# Power_Supply_V3.net
KiCad netlist of a schematic drawn in EAGLE
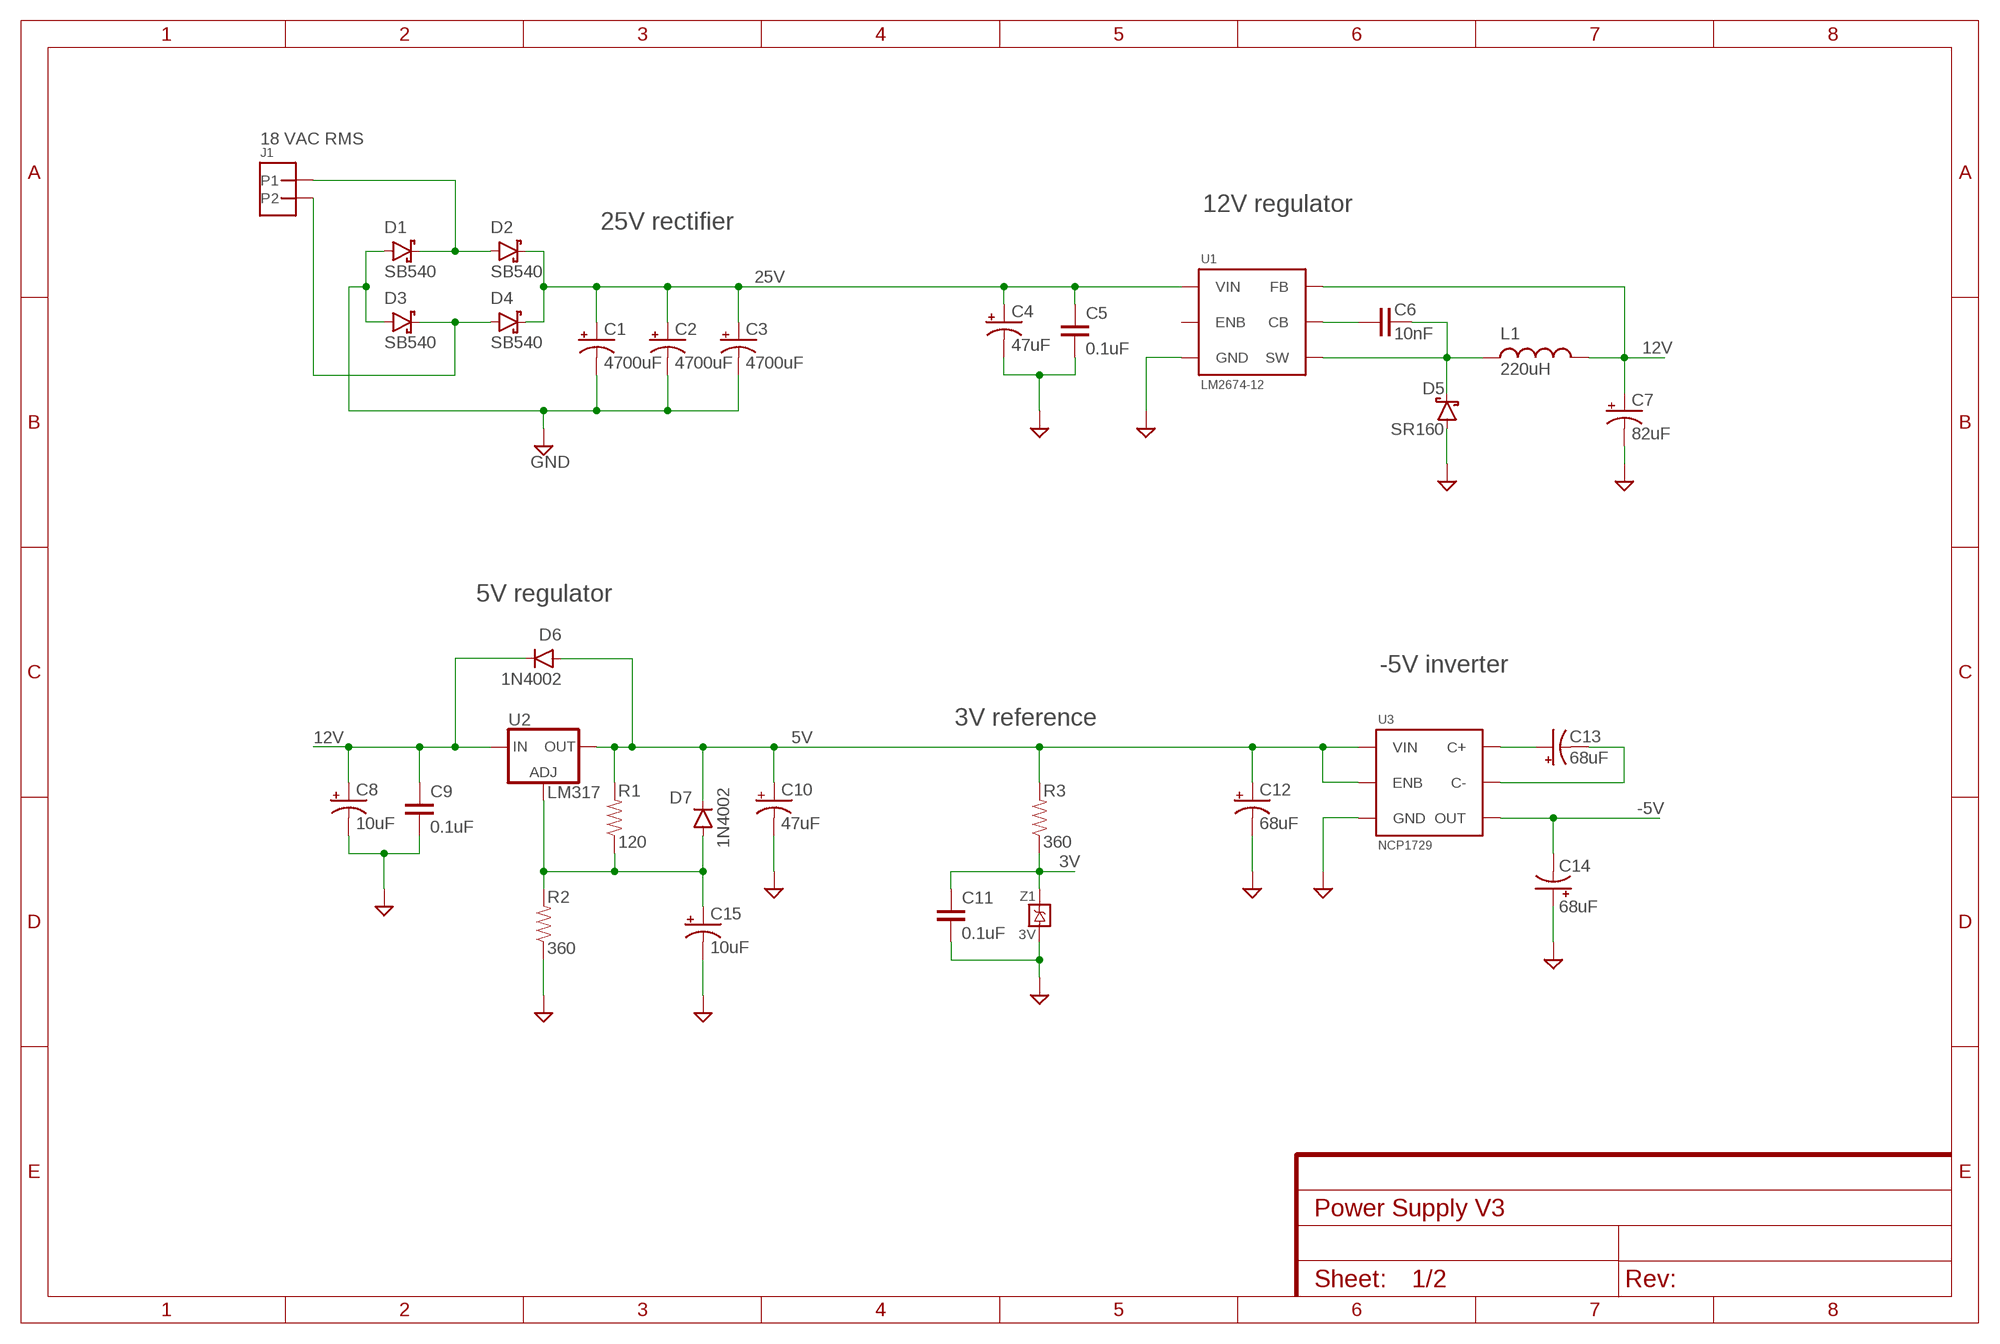
[diagram p0: schematic, sheet 1]
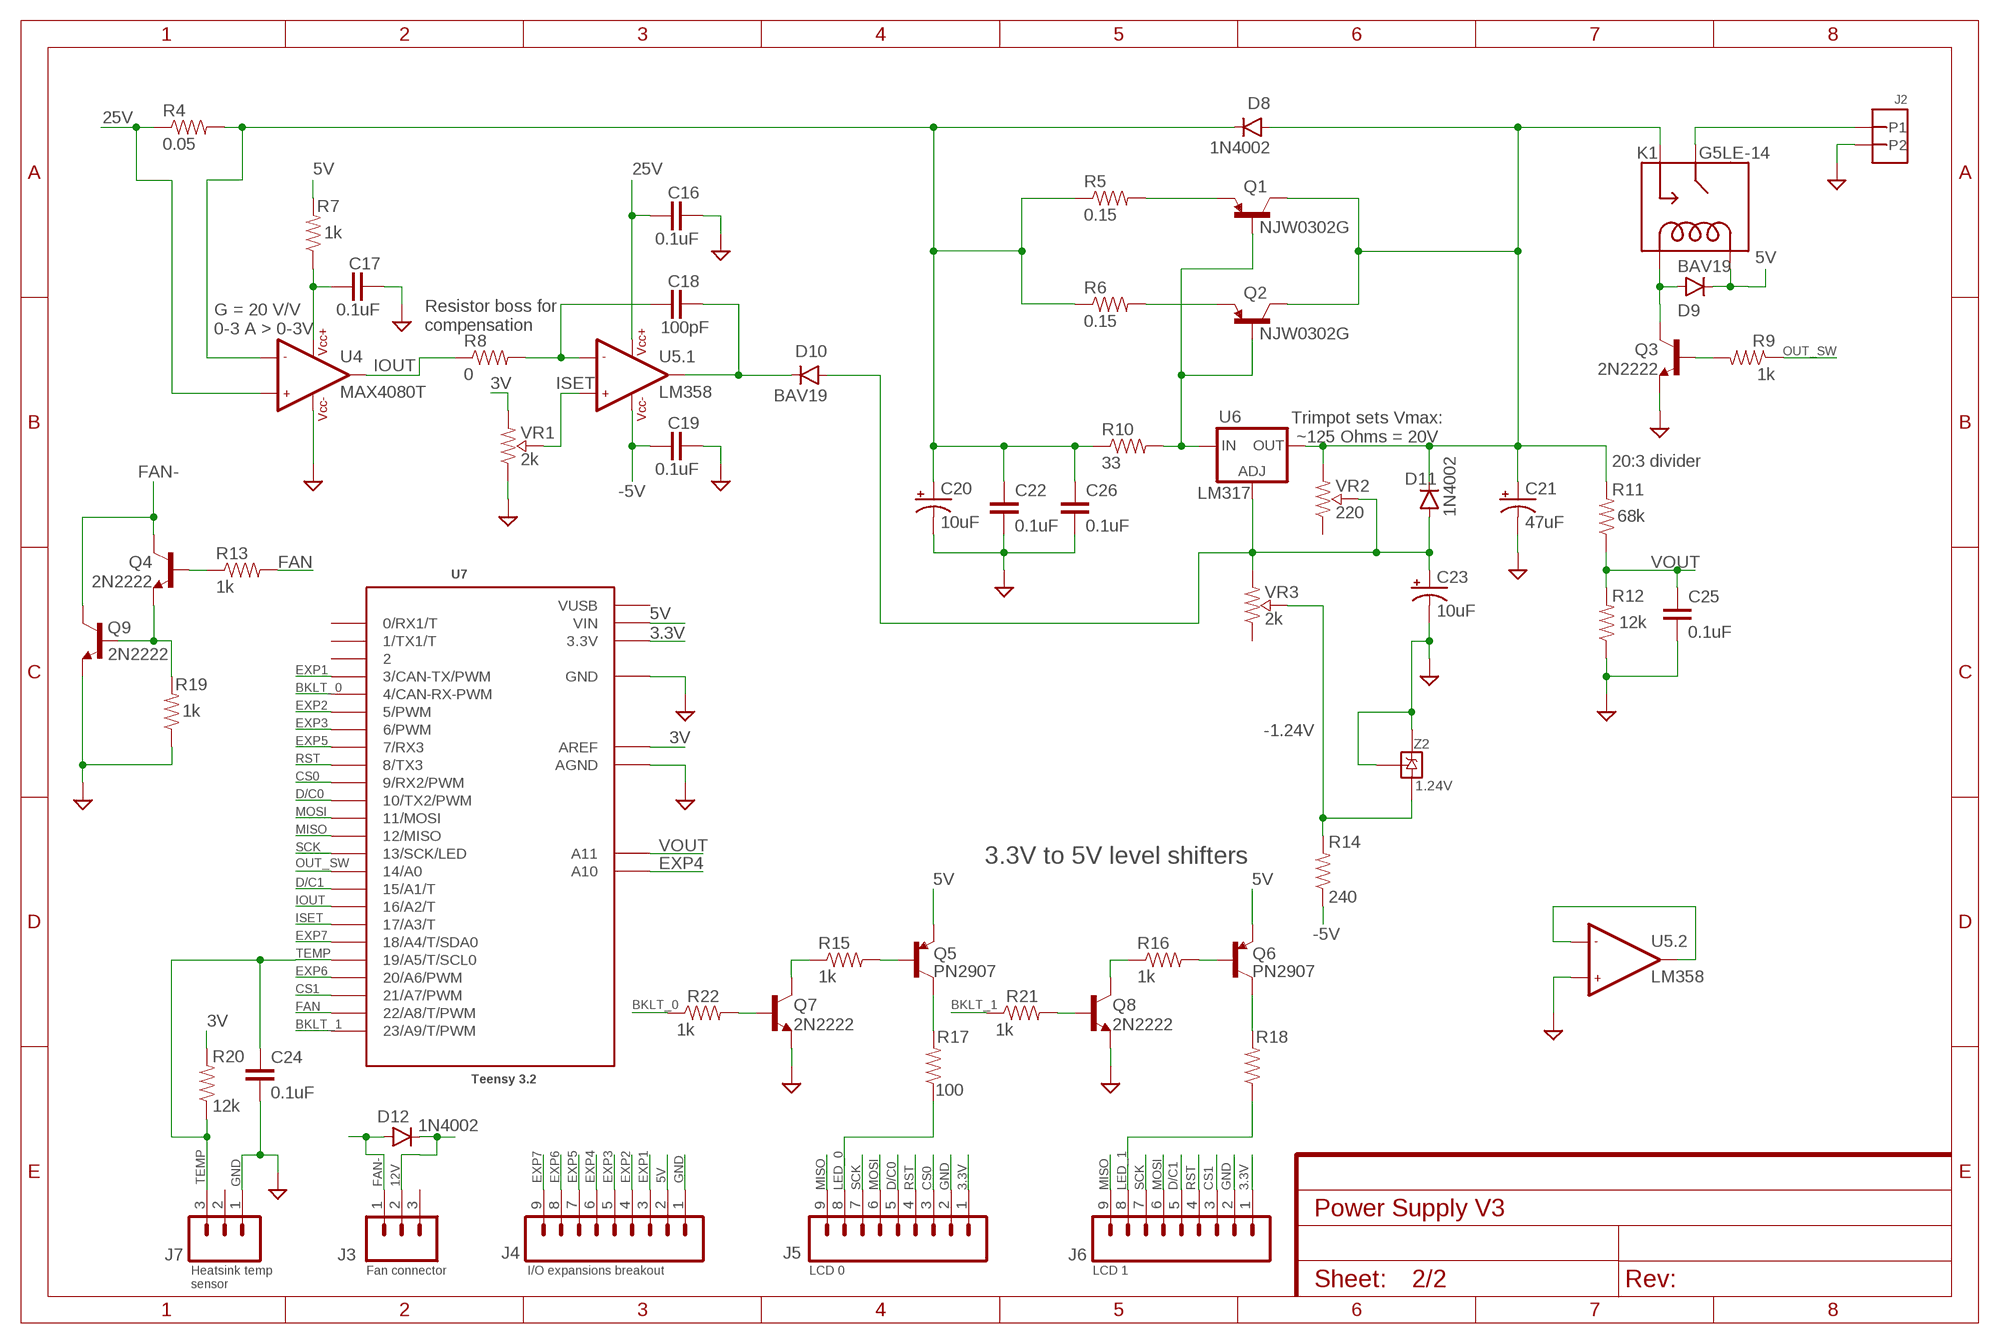
[diagram p1: schematic, sheet 2]

(export (version "E")
  (design (tool "Eeschema 10.0.6"))
  (components
    (comp (ref "C1")
      (value "4700uF")
      (footprint "eagle-import:10MM-LEAD_22MM-DIA")
      (libsource (lib "eagle-import") (part "RADIAL_POL10MM_LEAD-22MM_DIA"))
    )
    (comp (ref "C2")
      (value "4700uF")
      (footprint "eagle-import:10MM-LEAD_22MM-DIA")
      (libsource (lib "eagle-import") (part "RADIAL_POL10MM_LEAD-22MM_DIA"))
    )
    (comp (ref "C3")
      (value "4700uF")
      (footprint "eagle-import:10MM-LEAD_22MM-DIA")
      (libsource (lib "eagle-import") (part "RADIAL_POL10MM_LEAD-22MM_DIA"))
    )
    (comp (ref "C4")
      (value "47uF")
      (footprint "eagle-import:2.5MM_LEAD-6.3MM_DIA")
      (libsource (lib "eagle-import") (part "RADIAL_POL2.5MM_LEAD-6.3MM_DIA"))
    )
    (comp (ref "C5")
      (value "0.1uF")
      (footprint "eagle-import:0805")
      (libsource (lib "eagle-import") (part "NON_POL_0805/2012"))
    )
    (comp (ref "C6")
      (value "10nF")
      (footprint "eagle-import:1206")
      (libsource (lib "eagle-import") (part "NON_POL_1206/3216"))
    )
    (comp (ref "C7")
      (value "82uF")
      (footprint "eagle-import:2.5MM_LEAD-6.3MM_DIA")
      (libsource (lib "eagle-import") (part "RADIAL_POL2.5MM_LEAD-6.3MM_DIA"))
    )
    (comp (ref "C8")
      (value "10uF")
      (footprint "eagle-import:6032-28")
      (libsource (lib "eagle-import") (part "SMD_POL_6032"))
    )
    (comp (ref "C9")
      (value "0.1uF")
      (footprint "eagle-import:0805")
      (libsource (lib "eagle-import") (part "NON_POL_0805/2012"))
    )
    (comp (ref "C10")
      (value "47uF")
      (footprint "eagle-import:2.5MM_LEAD-6.3MM_DIA")
      (libsource (lib "eagle-import") (part "RADIAL_POL2.5MM_LEAD-6.3MM_DIA"))
    )
    (comp (ref "C11")
      (value "0.1uF")
      (footprint "eagle-import:0805")
      (libsource (lib "eagle-import") (part "NON_POL_0805/2012"))
    )
    (comp (ref "C12")
      (value "68uF")
      (footprint "eagle-import:ALUM_SMD_SMALL")
      (libsource (lib "eagle-import") (part "SMD_POL_NICHICON_RFS"))
    )
    (comp (ref "C13")
      (value "68uF")
      (footprint "eagle-import:ALUM_SMD_SMALL")
      (libsource (lib "eagle-import") (part "SMD_POL_NICHICON_RFS"))
    )
    (comp (ref "C14")
      (value "68uF")
      (footprint "eagle-import:ALUM_SMD_SMALL")
      (libsource (lib "eagle-import") (part "SMD_POL_NICHICON_RFS"))
    )
    (comp (ref "C15")
      (value "10uF")
      (footprint "eagle-import:6032-28")
      (libsource (lib "eagle-import") (part "SMD_POL_6032"))
    )
    (comp (ref "D1")
      (value "SB540")
      (footprint "eagle-import:DO201-15")
      (libsource (lib "eagle-import") (part "SCHOTTKY_DIODE_DO-201"))
    )
    (comp (ref "D2")
      (value "SB540")
      (footprint "eagle-import:DO201-15")
      (libsource (lib "eagle-import") (part "SCHOTTKY_DIODE_DO-201"))
    )
    (comp (ref "D3")
      (value "SB540")
      (footprint "eagle-import:DO201-15")
      (libsource (lib "eagle-import") (part "SCHOTTKY_DIODE_DO-201"))
    )
    (comp (ref "D4")
      (value "SB540")
      (footprint "eagle-import:DO201-15")
      (libsource (lib "eagle-import") (part "SCHOTTKY_DIODE_DO-201"))
    )
    (comp (ref "D5")
      (value "SR160")
      (footprint "eagle-import:DO41-10")
      (libsource (lib "eagle-import") (part "SCHOTTKY_DIODE_DO-41"))
    )
    (comp (ref "D6")
      (value "1N4002")
      (footprint "eagle-import:DO41-10")
      (libsource (lib "eagle-import") (part "THROUGH_HOLE_DO-41"))
    )
    (comp (ref "D7")
      (value "1N4002")
      (footprint "eagle-import:DO41-10")
      (libsource (lib "eagle-import") (part "THROUGH_HOLE_DO-41"))
    )
    (comp (ref "J1")
      (value "MOLEX_46999-0126")
      (footprint "eagle-import:2P_MOLEX_5566")
      (libsource (lib "eagle-import") (part "MOLEX_46999-0126"))
    )
    (comp (ref "L1")
      (value "220uH")
      (footprint "eagle-import:1200LRS")
      (libsource (lib "eagle-import") (part "1200LRS"))
    )
    (comp (ref "R1")
      (value "120")
      (footprint "eagle-import:1_4W_0.4")
      (libsource (lib "eagle-import") (part "THROUGH_HOLE_1/4W"))
    )
    (comp (ref "R2")
      (value "360")
      (footprint "eagle-import:1_4W_0.4")
      (libsource (lib "eagle-import") (part "THROUGH_HOLE_1/4W"))
    )
    (comp (ref "R3")
      (value "360")
      (footprint "eagle-import:1_4W_0.4")
      (libsource (lib "eagle-import") (part "THROUGH_HOLE_1/4W"))
    )
    (comp (ref "U1")
      (value "LM2674-12")
      (footprint "eagle-import:SOIC-8")
      (libsource (lib "eagle-import") (part "LM2674_SOIC-8"))
    )
    (comp (ref "U2")
      (value "LM317")
      (footprint "eagle-import:TO-220")
      (fields (field (name "SPICEMODEL") "LM317") (field (name "SPICEPREFIX") "X"))
      (libsource (lib "eagle-import") (part "LM317_TO-220"))
    )
    (comp (ref "U3")
      (value "NCP1729")
      (footprint "eagle-import:TSOP-6")
      (libsource (lib "eagle-import") (part "NCP1729"))
    )
    (comp (ref "Z1")
      (value "3V")
      (footprint "eagle-import:TO-92_AMMO")
      (libsource (lib "eagle-import") (part "LM4040_TO-92"))
    )
    (comp (ref "C16")
      (value "0.1uF")
      (footprint "eagle-import:0805")
      (libsource (lib "eagle-import") (part "NON_POL_0805/2012"))
    )
    (comp (ref "C17")
      (value "0.1uF")
      (footprint "eagle-import:0805")
      (libsource (lib "eagle-import") (part "NON_POL_0805/2012"))
    )
    (comp (ref "C18")
      (value "100pF")
      (footprint "eagle-import:2.54MM_LEAD")
      (libsource (lib "eagle-import") (part "NON_POL_2.5MM"))
    )
    (comp (ref "C19")
      (value "0.1uF")
      (footprint "eagle-import:0805")
      (libsource (lib "eagle-import") (part "NON_POL_0805/2012"))
    )
    (comp (ref "C20")
      (value "10uF")
      (footprint "eagle-import:6032-28")
      (libsource (lib "eagle-import") (part "SMD_POL_6032"))
    )
    (comp (ref "C21")
      (value "47uF")
      (footprint "eagle-import:2.5MM_LEAD-6.3MM_DIA")
      (libsource (lib "eagle-import") (part "RADIAL_POL2.5MM_LEAD-6.3MM_DIA"))
    )
    (comp (ref "C22")
      (value "0.1uF")
      (footprint "eagle-import:0805")
      (libsource (lib "eagle-import") (part "NON_POL_0805/2012"))
    )
    (comp (ref "C23")
      (value "10uF")
      (footprint "eagle-import:6032-28")
      (libsource (lib "eagle-import") (part "SMD_POL_6032"))
    )
    (comp (ref "C24")
      (value "0.1uF")
      (footprint "eagle-import:0805")
      (libsource (lib "eagle-import") (part "NON_POL_0805/2012"))
    )
    (comp (ref "C25")
      (value "0.1uF")
      (footprint "eagle-import:0805")
      (libsource (lib "eagle-import") (part "NON_POL_0805/2012"))
    )
    (comp (ref "C26")
      (value "0.1uF")
      (footprint "eagle-import:0805")
      (libsource (lib "eagle-import") (part "NON_POL_0805/2012"))
    )
    (comp (ref "D8")
      (value "1N4002")
      (footprint "eagle-import:DO41-10")
      (libsource (lib "eagle-import") (part "THROUGH_HOLE_DO-41"))
    )
    (comp (ref "D9")
      (value "BAV19")
      (footprint "eagle-import:DO35-10")
      (libsource (lib "eagle-import") (part "THROUGH_HOLE_DO-35"))
    )
    (comp (ref "D10")
      (value "BAV19")
      (footprint "eagle-import:DO35-10")
      (libsource (lib "eagle-import") (part "THROUGH_HOLE_DO-35"))
    )
    (comp (ref "D11")
      (value "1N4002")
      (footprint "eagle-import:DO41-10")
      (libsource (lib "eagle-import") (part "THROUGH_HOLE_DO-41"))
    )
    (comp (ref "D12")
      (value "1N4002")
      (footprint "eagle-import:DO41-10")
      (libsource (lib "eagle-import") (part "THROUGH_HOLE_DO-41"))
    )
    (comp (ref "J2")
      (value "MOLEX_46999-0126")
      (footprint "eagle-import:2P_MOLEX_5566")
      (libsource (lib "eagle-import") (part "MOLEX_46999-0126"))
    )
    (comp (ref "J3")
      (value "3P_XH2.54")
      (footprint "eagle-import:XH-3P_LOCK")
      (libsource (lib "eagle-import") (part "3P_XH2.54"))
    )
    (comp (ref "J4")
      (value "9P_XH2.54LOCK")
      (footprint "eagle-import:9P_XH2.54_LOCK")
      (libsource (lib "eagle-import") (part "9P_XH2.54LOCK"))
    )
    (comp (ref "J5")
      (value "9P_XH2.54LOCK")
      (footprint "eagle-import:9P_XH2.54_LOCK")
      (libsource (lib "eagle-import") (part "9P_XH2.54LOCK"))
    )
    (comp (ref "J6")
      (value "9P_XH2.54LOCK")
      (footprint "eagle-import:9P_XH2.54_LOCK")
      (libsource (lib "eagle-import") (part "9P_XH2.54LOCK"))
    )
    (comp (ref "J7")
      (value "3P_XH2.54")
      (footprint "eagle-import:XH-3P_LOCK")
      (libsource (lib "eagle-import") (part "3P_XH2.54"))
    )
    (comp (ref "K1")
      (value "G5LE-14")
      (footprint "eagle-import:SPST_RELAY_NO")
      (libsource (lib "eagle-import") (part "RELAY_G5LE-14"))
    )
    (comp (ref "Q1")
      (value "NJW0302G")
      (footprint "eagle-import:TO-247AD-V")
      (fields (field (name "SPICEMODEL") "NJW0302G") (field (name "SPICEPREFIX") "Q"))
      (libsource (lib "eagle-import") (part "PNP_NJW0302G"))
    )
    (comp (ref "Q2")
      (value "NJW0302G")
      (footprint "eagle-import:TO-247AD-V")
      (fields (field (name "SPICEMODEL") "NJW0302G") (field (name "SPICEPREFIX") "Q"))
      (libsource (lib "eagle-import") (part "PNP_NJW0302G"))
    )
    (comp (ref "Q3")
      (value "2N2222")
      (footprint "eagle-import:TO-92")
      (libsource (lib "eagle-import") (part "NPN_2N2222"))
    )
    (comp (ref "Q4")
      (value "2N2222")
      (footprint "eagle-import:TO-92")
      (libsource (lib "eagle-import") (part "NPN_2N2222"))
    )
    (comp (ref "Q5")
      (value "PN2907")
      (footprint "eagle-import:TO-92_AMMO")
      (libsource (lib "eagle-import") (part "PNP_PN2907"))
    )
    (comp (ref "Q6")
      (value "PN2907")
      (footprint "eagle-import:TO-92_AMMO")
      (libsource (lib "eagle-import") (part "PNP_PN2907"))
    )
    (comp (ref "Q7")
      (value "2N2222")
      (footprint "eagle-import:TO-92")
      (libsource (lib "eagle-import") (part "NPN_2N2222"))
    )
    (comp (ref "Q8")
      (value "2N2222")
      (footprint "eagle-import:TO-92")
      (libsource (lib "eagle-import") (part "NPN_2N2222"))
    )
    (comp (ref "Q9")
      (value "2N2222")
      (footprint "eagle-import:TO-92")
      (libsource (lib "eagle-import") (part "NPN_2N2222"))
    )
    (comp (ref "R4")
      (value "0.05")
      (footprint "eagle-import:2512")
      (libsource (lib "eagle-import") (part "SMD_2512"))
    )
    (comp (ref "R5")
      (value "0.15")
      (footprint "eagle-import:1_2W_0.5")
      (libsource (lib "eagle-import") (part "THROUGH_HOLE_1/2W"))
    )
    (comp (ref "R6")
      (value "0.15")
      (footprint "eagle-import:1_2W_0.5")
      (libsource (lib "eagle-import") (part "THROUGH_HOLE_1/2W"))
    )
    (comp (ref "R7")
      (value "1k")
      (footprint "eagle-import:1_4W_0.4")
      (fields (field (name "SPICEPREFIX") "R"))
      (libsource (lib "eagle-import") (part "THROUGH_HOLE_1/4W"))
    )
    (comp (ref "R8")
      (value "0")
      (footprint "eagle-import:1_4W_0.4")
      (libsource (lib "eagle-import") (part "THROUGH_HOLE_1/4W"))
    )
    (comp (ref "R9")
      (value "1k")
      (footprint "eagle-import:1_4W_0.4")
      (libsource (lib "eagle-import") (part "THROUGH_HOLE_1/4W"))
    )
    (comp (ref "R10")
      (value "33")
      (footprint "eagle-import:1_4W_0.4")
      (libsource (lib "eagle-import") (part "THROUGH_HOLE_1/4W"))
    )
    (comp (ref "R11")
      (value "68k")
      (footprint "eagle-import:0805")
      (libsource (lib "eagle-import") (part "SMD_0805"))
    )
    (comp (ref "R12")
      (value "12k")
      (footprint "eagle-import:0805")
      (libsource (lib "eagle-import") (part "SMD_0805"))
    )
    (comp (ref "R13")
      (value "1k")
      (footprint "eagle-import:1_4W_0.4")
      (libsource (lib "eagle-import") (part "THROUGH_HOLE_1/4W"))
    )
    (comp (ref "R14")
      (value "240")
      (footprint "eagle-import:1_4W_0.4")
      (libsource (lib "eagle-import") (part "THROUGH_HOLE_1/4W"))
    )
    (comp (ref "R15")
      (value "1k")
      (footprint "eagle-import:1_4W_0.4")
      (libsource (lib "eagle-import") (part "THROUGH_HOLE_1/4W"))
    )
    (comp (ref "R16")
      (value "1k")
      (footprint "eagle-import:1_4W_0.4")
      (libsource (lib "eagle-import") (part "THROUGH_HOLE_1/4W"))
    )
    (comp (ref "R17")
      (value "100")
      (footprint "eagle-import:1_4W_0.4")
      (libsource (lib "eagle-import") (part "THROUGH_HOLE_1/4W"))
    )
    (comp (ref "R18")
      (value "100")
      (footprint "eagle-import:1_4W_0.4")
      (libsource (lib "eagle-import") (part "THROUGH_HOLE_1/4W"))
    )
    (comp (ref "R19")
      (value "1k")
      (footprint "eagle-import:1_4W_0.4")
      (fields (field (name "SPICEPREFIX") "R"))
      (libsource (lib "eagle-import") (part "THROUGH_HOLE_1/4W"))
    )
    (comp (ref "R20")
      (value "12k")
      (footprint "eagle-import:0805")
      (libsource (lib "eagle-import") (part "SMD_0805"))
    )
    (comp (ref "R21")
      (value "1k")
      (footprint "eagle-import:1_4W_0.4")
      (libsource (lib "eagle-import") (part "THROUGH_HOLE_1/4W"))
    )
    (comp (ref "R22")
      (value "1k")
      (footprint "eagle-import:1_4W_0.4")
      (libsource (lib "eagle-import") (part "THROUGH_HOLE_1/4W"))
    )
    (comp (ref "U4")
      (value "MAX4080T")
      (footprint "eagle-import:SO08")
      (libsource (lib "eagle-import") (part "MAX4080"))
    )
    (comp (ref "U5")
      (value "LM358")
      (footprint "eagle-import:DIL-08")
      (libsource (lib "eagle-import") (part "OP-AMP_DUAL_LM358"))
    )
    (comp (ref "U6")
      (value "LM317")
      (footprint "eagle-import:TO-220")
      (fields (field (name "SPICEMODEL") "LM317") (field (name "SPICEPREFIX") "X"))
      (libsource (lib "eagle-import") (part "LM317_TO-220"))
    )
    (comp (ref "U7")
      (value "Teensy 3.2")
      (footprint "eagle-import:TEENSY3-DIL+4")
      (libsource (lib "eagle-import") (part "TEENSY_3.1_DIL+4"))
    )
    (comp (ref "VR1")
      (value "2k")
      (footprint "eagle-import:XH-3P_LOCK")
      (fields (field (name "SPICEMODEL") "POT") (field (name "SPICEPREFIX") "X"))
      (libsource (lib "eagle-import") (part "OFFBOARD_POTXH-3P_LOCK"))
    )
    (comp (ref "VR2")
      (value "220")
      (footprint "eagle-import:THROUGH_HOLE_TRIMPOT")
      (libsource (lib "eagle-import") (part "TRIM_POTS_THROUGH_HOLE_2.54MM"))
    )
    (comp (ref "VR3")
      (value "2k")
      (footprint "eagle-import:XH-3P_LOCK")
      (fields (field (name "SPICEMODEL") "POT") (field (name "SPICEPREFIX") "X"))
      (libsource (lib "eagle-import") (part "OFFBOARD_POTXH-3P_LOCK"))
    )
    (comp (ref "Z2")
      (value "1.24V")
      (footprint "eagle-import:TO-92_AMMO")
      (libsource (lib "eagle-import") (part "ADJ_VOLTAGE_REF_AZ431L"))
    )
  )
  (nets
    (net (code "1") (name "-1.24V") (class "Default")
      (node (ref "R14") (pin "P$2") (pinfunction "2_P$2") (pintype "passive"))
      (node (ref "VR3") (pin "2") (pinfunction "S_2") (pintype "passive"))
      (node (ref "Z2") (pin "2") (pinfunction "A_2") (pintype "bidirectional"))
    )
    (net (code "2") (name "-5V") (class "Default")
      (node (ref "C14") (pin "-") (pinfunction "-_-") (pintype "passive"))
      (node (ref "C19") (pin "1") (pinfunction "1_1") (pintype "passive"))
      (node (ref "R14") (pin "P$1") (pinfunction "1_P$1") (pintype "passive"))
      (node (ref "U3") (pin "1") (pinfunction "OUT_1") (pintype "bidirectional"))
      (node (ref "U5") (pin "4") (pinfunction "VCC-_4") (pintype "power_in"))
    )
    (net (code "3") (name "3.3V") (class "Default")
      (node (ref "J5") (pin "1") (pinfunction "1_1") (pintype "passive"))
      (node (ref "J6") (pin "1") (pinfunction "1_1") (pintype "passive"))
      (node (ref "U7") (pin "3.3V") (pinfunction "3.3V_3.3V") (pintype "power_in"))
    )
    (net (code "4") (name "3V") (class "Default")
      (node (ref "C11") (pin "1") (pinfunction "1_1") (pintype "passive"))
      (node (ref "R20") (pin "2") (pinfunction "2_2") (pintype "passive"))
      (node (ref "R3") (pin "P$1") (pinfunction "1_P$1") (pintype "passive"))
      (node (ref "U7") (pin "AREF") (pinfunction "AREF_AREF") (pintype "power_in"))
      (node (ref "VR1") (pin "3") (pinfunction "E_3") (pintype "passive"))
      (node (ref "Z1") (pin "2") (pinfunction "V+_2") (pintype "bidirectional"))
    )
    (net (code "5") (name "5V") (class "Default")
      (node (ref "C10") (pin "+") (pinfunction "+_+") (pintype "passive"))
      (node (ref "C12") (pin "+") (pinfunction "+_+") (pintype "passive"))
      (node (ref "D6") (pin "A") (pinfunction "A_A") (pintype "passive"))
      (node (ref "D7") (pin "C") (pinfunction "C_C") (pintype "passive"))
      (node (ref "D9") (pin "C") (pinfunction "C_C") (pintype "passive"))
      (node (ref "J4") (pin "2") (pinfunction "2_2") (pintype "passive"))
      (node (ref "K1") (pin "COIL2") (pinfunction "COIL2_COIL2") (pintype "bidirectional"))
      (node (ref "Q5") (pin "1") (pinfunction "E_1") (pintype "passive"))
      (node (ref "Q6") (pin "1") (pinfunction "E_1") (pintype "passive"))
      (node (ref "R1") (pin "P$2") (pinfunction "2_P$2") (pintype "passive"))
      (node (ref "R3") (pin "P$2") (pinfunction "2_P$2") (pintype "passive"))
      (node (ref "R7") (pin "P$2") (pinfunction "2_P$2") (pintype "passive"))
      (node (ref "U2") (pin "2") (pinfunction "OUT_2") (pintype "passive"))
      (node (ref "U3") (pin "2") (pinfunction "VIN_2") (pintype "bidirectional"))
      (node (ref "U3") (pin "5") (pinfunction "ENB_5") (pintype "bidirectional"))
      (node (ref "U7") (pin "VIN") (pinfunction "VIN_VIN") (pintype "power_in"))
    )
    (net (code "6") (name "12V") (class "Default")
      (node (ref "C7") (pin "+") (pinfunction "+_+") (pintype "passive"))
      (node (ref "C8") (pin "+") (pinfunction "+_+") (pintype "passive"))
      (node (ref "C9") (pin "1") (pinfunction "1_1") (pintype "passive"))
      (node (ref "D12") (pin "C") (pinfunction "C_C") (pintype "passive"))
      (node (ref "D6") (pin "C") (pinfunction "C_C") (pintype "passive"))
      (node (ref "J3") (pin "2") (pinfunction "2_2") (pintype "passive"))
      (node (ref "L1") (pin "3") (pinfunction "2_3") (pintype "passive"))
      (node (ref "U1") (pin "4") (pinfunction "FB_4") (pintype "bidirectional"))
      (node (ref "U2") (pin "3") (pinfunction "IN_3") (pintype "input"))
    )
    (net (code "7") (name "25V") (class "Default")
      (node (ref "C1") (pin "+") (pinfunction "+_+") (pintype "passive"))
      (node (ref "C16") (pin "1") (pinfunction "1_1") (pintype "passive"))
      (node (ref "C2") (pin "+") (pinfunction "+_+") (pintype "passive"))
      (node (ref "C3") (pin "+") (pinfunction "+_+") (pintype "passive"))
      (node (ref "C4") (pin "+") (pinfunction "+_+") (pintype "passive"))
      (node (ref "C5") (pin "1") (pinfunction "1_1") (pintype "passive"))
      (node (ref "D2") (pin "C") (pinfunction "C_C") (pintype "passive"))
      (node (ref "D4") (pin "C") (pinfunction "C_C") (pintype "passive"))
      (node (ref "R4") (pin "1") (pinfunction "1_1") (pintype "passive"))
      (node (ref "U1") (pin "7") (pinfunction "VIN_7") (pintype "bidirectional"))
      (node (ref "U4") (pin "1") (pinfunction "+IN1_1") (pintype "input"))
      (node (ref "U5") (pin "8") (pinfunction "VCC+_8") (pintype "power_in"))
    )
    (net (code "8") (name "BKLT_0") (class "Default")
      (node (ref "R22") (pin "P$1") (pinfunction "1_P$1") (pintype "passive"))
      (node (ref "U7") (pin "4") (pinfunction "4/CAN-RX-PWM_4") (pintype "bidirectional"))
    )
    (net (code "9") (name "BKLT_1") (class "Default")
      (node (ref "R21") (pin "P$1") (pinfunction "1_P$1") (pintype "passive"))
      (node (ref "U7") (pin "23/A9") (pinfunction "23/A9/T/PWM_23/A9") (pintype "bidirectional"))
    )
    (net (code "10") (name "CS0") (class "Default")
      (node (ref "J5") (pin "3") (pinfunction "3_3") (pintype "passive"))
      (node (ref "U7") (pin "9") (pinfunction "9/RX2/PWM_9") (pintype "bidirectional"))
    )
    (net (code "11") (name "CS1") (class "Default")
      (node (ref "J6") (pin "3") (pinfunction "3_3") (pintype "passive"))
      (node (ref "U7") (pin "21/A7") (pinfunction "21/A7/PWM_21/A7") (pintype "bidirectional"))
    )
    (net (code "12") (name "D{slash}C0") (class "Default")
      (node (ref "J5") (pin "5") (pinfunction "5_5") (pintype "passive"))
      (node (ref "U7") (pin "10") (pinfunction "10/TX2/PWM_10") (pintype "bidirectional"))
    )
    (net (code "13") (name "D{slash}C1") (class "Default")
      (node (ref "J6") (pin "5") (pinfunction "5_5") (pintype "passive"))
      (node (ref "U7") (pin "15/A1") (pinfunction "15/A1/T_15/A1") (pintype "bidirectional"))
    )
    (net (code "14") (name "EXP1") (class "Default")
      (node (ref "J4") (pin "3") (pinfunction "3_3") (pintype "passive"))
      (node (ref "U7") (pin "3") (pinfunction "3/CAN-TX/PWM_3") (pintype "bidirectional"))
    )
    (net (code "15") (name "EXP2") (class "Default")
      (node (ref "J4") (pin "4") (pinfunction "4_4") (pintype "passive"))
      (node (ref "U7") (pin "5") (pinfunction "5/PWM_5") (pintype "bidirectional"))
    )
    (net (code "16") (name "EXP3") (class "Default")
      (node (ref "J4") (pin "5") (pinfunction "5_5") (pintype "passive"))
      (node (ref "U7") (pin "6") (pinfunction "6/PWM_6") (pintype "bidirectional"))
    )
    (net (code "17") (name "EXP4") (class "Default")
      (node (ref "J4") (pin "6") (pinfunction "6_6") (pintype "passive"))
      (node (ref "U7") (pin "A10") (pinfunction "A10_A10") (pintype "bidirectional"))
    )
    (net (code "18") (name "EXP5") (class "Default")
      (node (ref "J4") (pin "7") (pinfunction "7_7") (pintype "passive"))
      (node (ref "U7") (pin "7") (pinfunction "7/RX3_7") (pintype "bidirectional"))
    )
    (net (code "19") (name "EXP6") (class "Default")
      (node (ref "J4") (pin "8") (pinfunction "8_8") (pintype "passive"))
      (node (ref "U7") (pin "20/A6") (pinfunction "20/A6/PWM_20/A6") (pintype "bidirectional"))
    )
    (net (code "20") (name "EXP7") (class "Default")
      (node (ref "J4") (pin "9") (pinfunction "9_9") (pintype "passive"))
      (node (ref "U7") (pin "18/A4") (pinfunction "18/A4/T/SDA0_18/A4") (pintype "bidirectional"))
    )
    (net (code "21") (name "FAN") (class "Default")
      (node (ref "R13") (pin "P$2") (pinfunction "2_P$2") (pintype "passive"))
      (node (ref "U7") (pin "22/A8") (pinfunction "22/A8/T/PWM_22/A8") (pintype "bidirectional"))
    )
    (net (code "22") (name "FAN-") (class "Default")
      (node (ref "D12") (pin "A") (pinfunction "A_A") (pintype "passive"))
      (node (ref "J3") (pin "1") (pinfunction "1_1") (pintype "passive"))
      (node (ref "Q4") (pin "3") (pinfunction "C_3") (pintype "passive"))
      (node (ref "Q9") (pin "3") (pinfunction "C_3") (pintype "passive"))
    )
    (net (code "23") (name "GND") (class "Default")
      (node (ref "C1") (pin "-") (pinfunction "-_-") (pintype "passive"))
      (node (ref "C10") (pin "-") (pinfunction "-_-") (pintype "passive"))
      (node (ref "C11") (pin "2") (pinfunction "2_2") (pintype "passive"))
      (node (ref "C12") (pin "-") (pinfunction "-_-") (pintype "passive"))
      (node (ref "C14") (pin "+") (pinfunction "+_+") (pintype "passive"))
      (node (ref "C15") (pin "-") (pinfunction "-_-") (pintype "passive"))
      (node (ref "C16") (pin "2") (pinfunction "2_2") (pintype "passive"))
      (node (ref "C17") (pin "2") (pinfunction "2_2") (pintype "passive"))
      (node (ref "C19") (pin "2") (pinfunction "2_2") (pintype "passive"))
      (node (ref "C2") (pin "-") (pinfunction "-_-") (pintype "passive"))
      (node (ref "C20") (pin "-") (pinfunction "-_-") (pintype "passive"))
      (node (ref "C21") (pin "-") (pinfunction "-_-") (pintype "passive"))
      (node (ref "C22") (pin "2") (pinfunction "2_2") (pintype "passive"))
      (node (ref "C23") (pin "-") (pinfunction "-_-") (pintype "passive"))
      (node (ref "C24") (pin "2") (pinfunction "2_2") (pintype "passive"))
      (node (ref "C25") (pin "2") (pinfunction "2_2") (pintype "passive"))
      (node (ref "C26") (pin "2") (pinfunction "2_2") (pintype "passive"))
      (node (ref "C3") (pin "-") (pinfunction "-_-") (pintype "passive"))
      (node (ref "C4") (pin "-") (pinfunction "-_-") (pintype "passive"))
      (node (ref "C5") (pin "2") (pinfunction "2_2") (pintype "passive"))
      (node (ref "C7") (pin "-") (pinfunction "-_-") (pintype "passive"))
      (node (ref "C8") (pin "-") (pinfunction "-_-") (pintype "passive"))
      (node (ref "C9") (pin "2") (pinfunction "2_2") (pintype "passive"))
      (node (ref "D1") (pin "A") (pinfunction "A_A") (pintype "passive"))
      (node (ref "D3") (pin "A") (pinfunction "A_A") (pintype "passive"))
      (node (ref "D5") (pin "A") (pinfunction "A_A") (pintype "passive"))
      (node (ref "J2") (pin "2") (pinfunction "P2_2") (pintype "power_in"))
      (node (ref "J4") (pin "1") (pinfunction "1_1") (pintype "passive"))
      (node (ref "J5") (pin "2") (pinfunction "2_2") (pintype "passive"))
      (node (ref "J6") (pin "2") (pinfunction "2_2") (pintype "passive"))
      (node (ref "J7") (pin "1") (pinfunction "1_1") (pintype "passive"))
      (node (ref "Q3") (pin "1") (pinfunction "E_1") (pintype "passive"))
      (node (ref "Q7") (pin "1") (pinfunction "E_1") (pintype "passive"))
      (node (ref "Q8") (pin "1") (pinfunction "E_1") (pintype "passive"))
      (node (ref "Q9") (pin "1") (pinfunction "E_1") (pintype "passive"))
      (node (ref "R12") (pin "1") (pinfunction "1_1") (pintype "passive"))
      (node (ref "R19") (pin "P$1") (pinfunction "1_P$1") (pintype "passive"))
      (node (ref "R2") (pin "P$1") (pinfunction "1_P$1") (pintype "passive"))
      (node (ref "U1") (pin "6") (pinfunction "GND_6") (pintype "bidirectional"))
      (node (ref "U3") (pin "4") (pinfunction "GND_4") (pintype "bidirectional"))
      (node (ref "U4") (pin "4") (pinfunction "VCC-_4") (pintype "power_in"))
      (node (ref "U5") (pin "5") (pinfunction "+IN2_5") (pintype "input"))
      (node (ref "U7") (pin "AGND") (pinfunction "AGND_AGND") (pintype "power_in"))
      (node (ref "U7") (pin "GND") (pinfunction "GND_GND") (pintype "power_in"))
      (node (ref "VR1") (pin "1") (pinfunction "A_1") (pintype "passive"))
      (node (ref "Z1") (pin "1") (pinfunction "V-_1") (pintype "bidirectional"))
      (node (ref "Z2") (pin "1") (pinfunction "REF_1") (pintype "bidirectional"))
      (node (ref "Z2") (pin "3") (pinfunction "C_3") (pintype "bidirectional"))
    )
    (net (code "24") (name "IN") (class "Default")
      (node (ref "Q1") (pin "1") (pinfunction "B_1") (pintype "passive"))
      (node (ref "Q2") (pin "1") (pinfunction "B_1") (pintype "passive"))
      (node (ref "R10") (pin "P$2") (pinfunction "2_P$2") (pintype "passive"))
      (node (ref "U6") (pin "3") (pinfunction "IN_3") (pintype "input"))
    )
    (net (code "25") (name "IOUT") (class "Default")
      (node (ref "R8") (pin "P$1") (pinfunction "1_P$1") (pintype "passive"))
      (node (ref "U4") (pin "5") (pinfunction "OUT1_5") (pintype "output"))
      (node (ref "U7") (pin "16/A2") (pinfunction "16/A2/T_16/A2") (pintype "bidirectional"))
    )
    (net (code "26") (name "ISET") (class "Default")
      (node (ref "U5") (pin "3") (pinfunction "+IN1_3") (pintype "input"))
      (node (ref "U7") (pin "17/A3") (pinfunction "17/A3/T_17/A3") (pintype "bidirectional"))
      (node (ref "VR1") (pin "2") (pinfunction "S_2") (pintype "passive"))
    )
    (net (code "27") (name "LED_0") (class "Default")
      (node (ref "J5") (pin "8") (pinfunction "8_8") (pintype "passive"))
      (node (ref "R17") (pin "P$1") (pinfunction "1_P$1") (pintype "passive"))
    )
    (net (code "28") (name "LED_1") (class "Default")
      (node (ref "J6") (pin "8") (pinfunction "8_8") (pintype "passive"))
      (node (ref "R18") (pin "P$1") (pinfunction "1_P$1") (pintype "passive"))
    )
    (net (code "29") (name "MISO") (class "Default")
      (node (ref "J5") (pin "9") (pinfunction "9_9") (pintype "passive"))
      (node (ref "J6") (pin "9") (pinfunction "9_9") (pintype "passive"))
      (node (ref "U7") (pin "12") (pinfunction "12/MISO_12") (pintype "bidirectional"))
    )
    (net (code "30") (name "MOSI") (class "Default")
      (node (ref "J5") (pin "6") (pinfunction "6_6") (pintype "passive"))
      (node (ref "J6") (pin "6") (pinfunction "6_6") (pintype "passive"))
      (node (ref "U7") (pin "11") (pinfunction "11/MOSI_11") (pintype "bidirectional"))
    )
    (net (code "34") (name "Net-(J1-P1)") (class "Default")
      (node (ref "D1") (pin "C") (pinfunction "C_C") (pintype "passive"))
      (node (ref "D2") (pin "A") (pinfunction "A_A") (pintype "passive"))
      (node (ref "J1") (pin "1") (pinfunction "P1_1") (pintype "power_in"))
    )
    (net (code "35") (name "Net-(J1-P2)") (class "Default")
      (node (ref "D3") (pin "C") (pinfunction "C_C") (pintype "passive"))
      (node (ref "D4") (pin "A") (pinfunction "A_A") (pintype "passive"))
      (node (ref "J1") (pin "2") (pinfunction "P2_2") (pintype "power_in"))
    )
    (net (code "36") (name "Net-(J2-P1)") (class "Default")
      (node (ref "J2") (pin "1") (pinfunction "P1_1") (pintype "power_in"))
      (node (ref "K1") (pin "COM") (pinfunction "MAIN_COM") (pintype "bidirectional"))
    )
    (net (code "37") (name "Net-(Q1-E)") (class "Default")
      (node (ref "Q1") (pin "3") (pinfunction "E_3") (pintype "passive"))
      (node (ref "R5") (pin "P$2") (pinfunction "2_P$2") (pintype "passive"))
    )
    (net (code "38") (name "Net-(Q2-E)") (class "Default")
      (node (ref "Q2") (pin "3") (pinfunction "E_3") (pintype "passive"))
      (node (ref "R6") (pin "P$2") (pinfunction "2_P$2") (pintype "passive"))
    )
    (net (code "39") (name "Net-(Q3-B)") (class "Default")
      (node (ref "Q3") (pin "2") (pinfunction "B_2") (pintype "passive"))
      (node (ref "R9") (pin "P$2") (pinfunction "2_P$2") (pintype "passive"))
    )
    (net (code "40") (name "Net-(Q3-C)") (class "Default")
      (node (ref "D9") (pin "A") (pinfunction "A_A") (pintype "passive"))
      (node (ref "K1") (pin "COIL1") (pinfunction "COIL1_COIL1") (pintype "bidirectional"))
      (node (ref "Q3") (pin "3") (pinfunction "C_3") (pintype "passive"))
    )
    (net (code "41") (name "Net-(Q4-B)") (class "Default")
      (node (ref "Q4") (pin "2") (pinfunction "B_2") (pintype "passive"))
      (node (ref "R13") (pin "P$1") (pinfunction "1_P$1") (pintype "passive"))
    )
    (net (code "42") (name "Net-(Q4-E)") (class "Default")
      (node (ref "Q4") (pin "1") (pinfunction "E_1") (pintype "passive"))
      (node (ref "Q9") (pin "2") (pinfunction "B_2") (pintype "passive"))
      (node (ref "R19") (pin "P$2") (pinfunction "2_P$2") (pintype "passive"))
    )
    (net (code "43") (name "Net-(Q5-B)") (class "Default")
      (node (ref "Q5") (pin "2") (pinfunction "B_2") (pintype "passive"))
      (node (ref "R15") (pin "P$2") (pinfunction "2_P$2") (pintype "passive"))
    )
    (net (code "44") (name "Net-(Q5-C)") (class "Default")
      (node (ref "Q5") (pin "3") (pinfunction "C_3") (pintype "passive"))
      (node (ref "R17") (pin "P$2") (pinfunction "2_P$2") (pintype "passive"))
    )
    (net (code "45") (name "Net-(Q6-B)") (class "Default")
      (node (ref "Q6") (pin "2") (pinfunction "B_2") (pintype "passive"))
      (node (ref "R16") (pin "P$2") (pinfunction "2_P$2") (pintype "passive"))
    )
    (net (code "46") (name "Net-(Q6-C)") (class "Default")
      (node (ref "Q6") (pin "3") (pinfunction "C_3") (pintype "passive"))
      (node (ref "R18") (pin "P$2") (pinfunction "2_P$2") (pintype "passive"))
    )
    (net (code "47") (name "Net-(Q7-B)") (class "Default")
      (node (ref "Q7") (pin "2") (pinfunction "B_2") (pintype "passive"))
      (node (ref "R22") (pin "P$2") (pinfunction "2_P$2") (pintype "passive"))
    )
    (net (code "48") (name "Net-(Q7-C)") (class "Default")
      (node (ref "Q7") (pin "3") (pinfunction "C_3") (pintype "passive"))
      (node (ref "R15") (pin "P$1") (pinfunction "1_P$1") (pintype "passive"))
    )
    (net (code "49") (name "Net-(Q8-B)") (class "Default")
      (node (ref "Q8") (pin "2") (pinfunction "B_2") (pintype "passive"))
      (node (ref "R21") (pin "P$2") (pinfunction "2_P$2") (pintype "passive"))
    )
    (net (code "50") (name "Net-(Q8-C)") (class "Default")
      (node (ref "Q8") (pin "3") (pinfunction "C_3") (pintype "passive"))
      (node (ref "R16") (pin "P$1") (pinfunction "1_P$1") (pintype "passive"))
    )
    (net (code "51") (name "Net-(R1-1)") (class "Default")
      (node (ref "C15") (pin "+") (pinfunction "+_+") (pintype "passive"))
      (node (ref "D7") (pin "A") (pinfunction "A_A") (pintype "passive"))
      (node (ref "R1") (pin "P$1") (pinfunction "1_P$1") (pintype "passive"))
      (node (ref "R2") (pin "P$2") (pinfunction "2_P$2") (pintype "passive"))
      (node (ref "U2") (pin "1") (pinfunction "ADJ_1") (pintype "input"))
    )
    (net (code "52") (name "Net-(R7-1)") (class "Default")
      (node (ref "C17") (pin "1") (pinfunction "1_1") (pintype "passive"))
      (node (ref "R7") (pin "P$1") (pinfunction "1_P$1") (pintype "passive"))
      (node (ref "U4") (pin "2") (pinfunction "VCC+_2") (pintype "power_in"))
    )
    (net (code "53") (name "Net-(R8-2)") (class "Default")
      (node (ref "C18") (pin "1") (pinfunction "1_1") (pintype "passive"))
      (node (ref "R8") (pin "P$2") (pinfunction "2_P$2") (pintype "passive"))
      (node (ref "U5") (pin "2") (pinfunction "-IN1_2") (pintype "input"))
    )
    (net (code "54") (name "Net-(R10-1)") (class "Default")
      (node (ref "C20") (pin "+") (pinfunction "+_+") (pintype "passive"))
      (node (ref "C22") (pin "1") (pinfunction "1_1") (pintype "passive"))
      (node (ref "C26") (pin "1") (pinfunction "1_1") (pintype "passive"))
      (node (ref "D8") (pin "C") (pinfunction "C_C") (pintype "passive"))
      (node (ref "R10") (pin "P$1") (pinfunction "1_P$1") (pintype "passive"))
      (node (ref "R4") (pin "2") (pinfunction "2_2") (pintype "passive"))
      (node (ref "R5") (pin "P$1") (pinfunction "1_P$1") (pintype "passive"))
      (node (ref "R6") (pin "P$1") (pinfunction "1_P$1") (pintype "passive"))
      (node (ref "U4") (pin "8") (pinfunction "-IN1_8") (pintype "input"))
    )
    (net (code "55") (name "Net-(U1-CB)") (class "Default")
      (node (ref "C6") (pin "1") (pinfunction "1_1") (pintype "passive"))
      (node (ref "U1") (pin "1") (pinfunction "CB_1") (pintype "bidirectional"))
    )
    (net (code "56") (name "Net-(U1-SW)") (class "Default")
      (node (ref "C6") (pin "2") (pinfunction "2_2") (pintype "passive"))
      (node (ref "D5") (pin "C") (pinfunction "C_C") (pintype "passive"))
      (node (ref "L1") (pin "1") (pinfunction "1_1") (pintype "passive"))
      (node (ref "U1") (pin "8") (pinfunction "SW_8") (pintype "bidirectional"))
    )
    (net (code "57") (name "Net-(U3-C+)") (class "Default")
      (node (ref "C13") (pin "+") (pinfunction "+_+") (pintype "passive"))
      (node (ref "U3") (pin "6") (pinfunction "C+_6") (pintype "bidirectional"))
    )
    (net (code "58") (name "Net-(U3-C-)") (class "Default")
      (node (ref "C13") (pin "-") (pinfunction "-_-") (pintype "passive"))
      (node (ref "U3") (pin "3") (pinfunction "C-_3") (pintype "bidirectional"))
    )
    (net (code "59") (name "Net-(U5A-OUT1)") (class "Default")
      (node (ref "C18") (pin "2") (pinfunction "2_2") (pintype "passive"))
      (node (ref "D10") (pin "C") (pinfunction "C_C") (pintype "passive"))
      (node (ref "U5") (pin "1") (pinfunction "OUT1_1") (pintype "output"))
    )
    (net (code "60") (name "Net-(U5B--IN2)") (class "Default")
      (node (ref "U5") (pin "6") (pinfunction "-IN2_6") (pintype "input"))
      (node (ref "U5") (pin "7") (pinfunction "OUT2_7") (pintype "output"))
    )
    (net (code "61") (name "OUT") (class "Default")
      (node (ref "C21") (pin "+") (pinfunction "+_+") (pintype "passive"))
      (node (ref "D11") (pin "C") (pinfunction "C_C") (pintype "passive"))
      (node (ref "D8") (pin "A") (pinfunction "A_A") (pintype "passive"))
      (node (ref "K1") (pin "NO") (pinfunction "NO_NO") (pintype "bidirectional"))
      (node (ref "Q1") (pin "2") (pinfunction "C_2") (pintype "passive"))
      (node (ref "Q2") (pin "2") (pinfunction "C_2") (pintype "passive"))
      (node (ref "R11") (pin "2") (pinfunction "2_2") (pintype "passive"))
      (node (ref "U6") (pin "2") (pinfunction "OUT_2") (pintype "passive"))
      (node (ref "VR2") (pin "3") (pinfunction "E_3") (pintype "passive"))
    )
    (net (code "62") (name "OUT_SW") (class "Default")
      (node (ref "R9") (pin "P$1") (pinfunction "1_P$1") (pintype "passive"))
      (node (ref "U7") (pin "14/A0") (pinfunction "14/A0_14/A0") (pintype "bidirectional"))
    )
    (net (code "63") (name "RST") (class "Default")
      (node (ref "J5") (pin "4") (pinfunction "4_4") (pintype "passive"))
      (node (ref "J6") (pin "4") (pinfunction "4_4") (pintype "passive"))
      (node (ref "U7") (pin "8") (pinfunction "8/TX3_8") (pintype "bidirectional"))
    )
    (net (code "64") (name "SCK") (class "Default")
      (node (ref "J5") (pin "7") (pinfunction "7_7") (pintype "passive"))
      (node (ref "J6") (pin "7") (pinfunction "7_7") (pintype "passive"))
      (node (ref "U7") (pin "13") (pinfunction "13/SCK/LED_13") (pintype "bidirectional"))
    )
    (net (code "65") (name "SET") (class "Default")
      (node (ref "C23") (pin "+") (pinfunction "+_+") (pintype "passive"))
      (node (ref "D10") (pin "A") (pinfunction "A_A") (pintype "passive"))
      (node (ref "D11") (pin "A") (pinfunction "A_A") (pintype "passive"))
      (node (ref "U6") (pin "1") (pinfunction "ADJ_1") (pintype "input"))
      (node (ref "VR2") (pin "2") (pinfunction "S_2") (pintype "passive"))
      (node (ref "VR3") (pin "3") (pinfunction "E_3") (pintype "passive"))
    )
    (net (code "66") (name "TEMP") (class "Default")
      (node (ref "C24") (pin "1") (pinfunction "1_1") (pintype "passive"))
      (node (ref "J7") (pin "3") (pinfunction "3_3") (pintype "passive"))
      (node (ref "R20") (pin "1") (pinfunction "1_1") (pintype "passive"))
      (node (ref "U7") (pin "19/A5") (pinfunction "19/A5/T/SCL0_19/A5") (pintype "bidirectional"))
    )
    (net (code "67") (name "VOUT") (class "Default")
      (node (ref "C25") (pin "1") (pinfunction "1_1") (pintype "passive"))
      (node (ref "R11") (pin "1") (pinfunction "1_1") (pintype "passive"))
      (node (ref "R12") (pin "2") (pinfunction "2_2") (pintype "passive"))
      (node (ref "U7") (pin "A11") (pinfunction "A11_A11") (pintype "bidirectional"))
    )
    (net (code "68") (name "VUSB") (class "Default")
      (node (ref "U7") (pin "VUSB") (pinfunction "VUSB_VUSB") (pintype "power_in"))
    )
    (net (code "69") (name "unconnected-(J3-Pad3)") (class "Default")
      (node (ref "J3") (pin "3") (pinfunction "3_3") (pintype "passive"))
    )
    (net (code "70") (name "unconnected-(J7-Pad2)") (class "Default")
      (node (ref "J7") (pin "2") (pinfunction "2_2") (pintype "passive"))
    )
    (net (code "71") (name "unconnected-(U1-ENB-Pad5)") (class "Default")
      (node (ref "U1") (pin "5") (pinfunction "ENB_5") (pintype "bidirectional"))
    )
    (net (code "72") (name "unconnected-(U7-0{slash}RX1{slash}T-Pad0)") (class "Default")
      (node (ref "U7") (pin "0") (pinfunction "0/RX1/T_0") (pintype "bidirectional"))
    )
    (net (code "73") (name "unconnected-(U7-1{slash}TX1{slash}T-Pad1)") (class "Default")
      (node (ref "U7") (pin "1") (pinfunction "1/TX1/T_1") (pintype "bidirectional"))
    )
    (net (code "74") (name "unconnected-(U7-Pad2)") (class "Default")
      (node (ref "U7") (pin "2") (pinfunction "2_2") (pintype "bidirectional"))
    )
    (net (code "75") (name "unconnected-(VR2-A-Pad1)") (class "Default")
      (node (ref "VR2") (pin "1") (pinfunction "A_1") (pintype "passive"))
    )
    (net (code "76") (name "unconnected-(VR3-A-Pad1)") (class "Default")
      (node (ref "VR3") (pin "1") (pinfunction "A_1") (pintype "passive"))
    )
  )
)
